# SH1_-_Power.net
KiCad netlist of a schematic drawn in Altium Designer
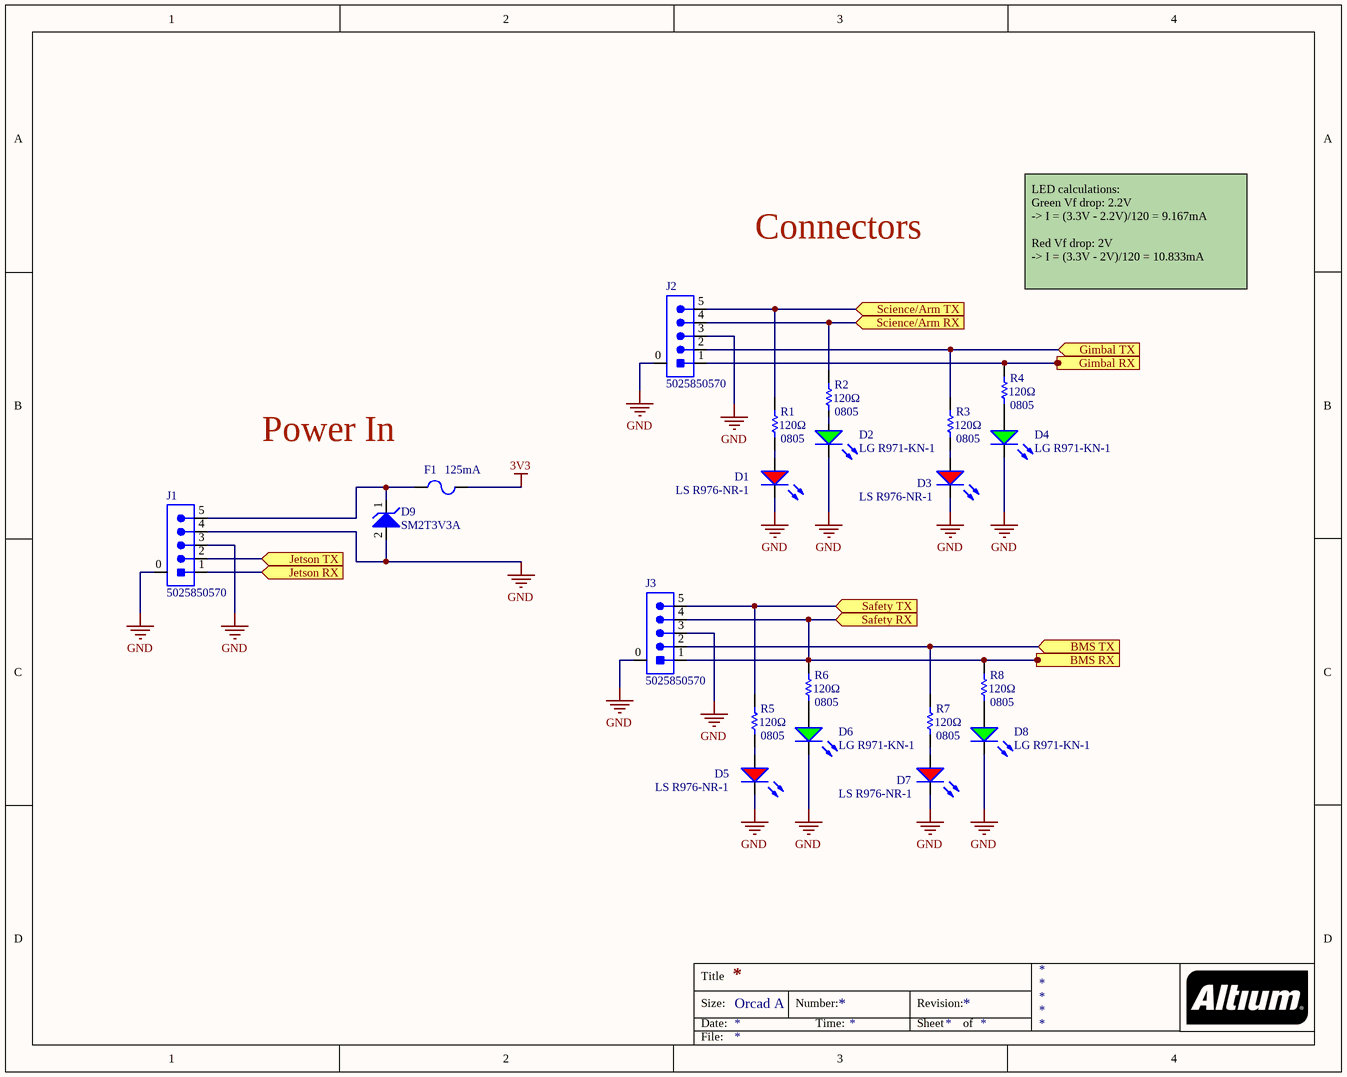
[diagram p0: SH1 - Power.SchDoc]

(export (version "E")
  (design (tool "Eeschema 10.0.6"))
  (components
    (comp (ref "D1")
      (value "LS R976-NR-1")
      (footprint "LED_0805_LINE")
      (description "LED RED DIFFUSED 0805 SMD")
      (fields (field (name "MANUFACTURER PART NUMBER 1") "LS R976-NR-1"))
      (libsource (lib "UWRT_Schematic_Library_2020") (part "DIO_LED_R"))
    )
    (comp (ref "D2")
      (value "LG R971-KN-1")
      (footprint "LED_0805_LINE")
      (description "LED GREEN DIFFUSED 0805 SMD")
      (fields (field (name "MANUFACTURER PART NUMBER 1") "LG R971-KN-1"))
      (libsource (lib "UWRT_Schematic_Library_2020") (part "DIO_LED_G"))
    )
    (comp (ref "D3")
      (value "LS R976-NR-1")
      (footprint "LED_0805_LINE")
      (description "LED RED DIFFUSED 0805 SMD")
      (fields (field (name "MANUFACTURER PART NUMBER 1") "LS R976-NR-1"))
      (libsource (lib "UWRT_Schematic_Library_2020") (part "DIO_LED_R"))
    )
    (comp (ref "D4")
      (value "LG R971-KN-1")
      (footprint "LED_0805_LINE")
      (description "LED GREEN DIFFUSED 0805 SMD")
      (fields (field (name "MANUFACTURER PART NUMBER 1") "LG R971-KN-1"))
      (libsource (lib "UWRT_Schematic_Library_2020") (part "DIO_LED_G"))
    )
    (comp (ref "D5")
      (value "LS R976-NR-1")
      (footprint "LED_0805_LINE")
      (description "LED RED DIFFUSED 0805 SMD")
      (fields (field (name "MANUFACTURER PART NUMBER 1") "LS R976-NR-1"))
      (libsource (lib "UWRT_Schematic_Library_2020") (part "DIO_LED_R"))
    )
    (comp (ref "D6")
      (value "LG R971-KN-1")
      (footprint "LED_0805_LINE")
      (description "LED GREEN DIFFUSED 0805 SMD")
      (fields (field (name "MANUFACTURER PART NUMBER 1") "LG R971-KN-1"))
      (libsource (lib "UWRT_Schematic_Library_2020") (part "DIO_LED_G"))
    )
    (comp (ref "D7")
      (value "LS R976-NR-1")
      (footprint "LED_0805_LINE")
      (description "LED RED DIFFUSED 0805 SMD")
      (fields (field (name "MANUFACTURER PART NUMBER 1") "LS R976-NR-1"))
      (libsource (lib "UWRT_Schematic_Library_2020") (part "DIO_LED_R"))
    )
    (comp (ref "D8")
      (value "LG R971-KN-1")
      (footprint "LED_0805_LINE")
      (description "LED GREEN DIFFUSED 0805 SMD")
      (fields (field (name "MANUFACTURER PART NUMBER 1") "LG R971-KN-1"))
      (libsource (lib "UWRT_Schematic_Library_2020") (part "DIO_LED_G"))
    )
    (comp (ref "D9")
      (value "TVS_DIODE_UNIDIR_3.3V")
      (footprint "TVS_DIODE_UNIDIR")
      (description "TVS DIODE 3.3V 6.8V DO216AA")
      (fields
        (field (name "MANUFACTURER") "STMicroelectronics")
        (field (name "MANUFACTURER PART NUMBER") "SM2T3V3A")
      )
      (libsource (lib "UWRT_Schematic_Library_2020") (part "TVS_DIODE_UNIDIR_3.3V"))
    )
    (comp (ref "F1")
      (value "FUSE_125mA_1206")
      (footprint "FUSE_1206")
      (description "FUSE SMD 125mA 125V")
      (fields (field (name "CURRENT RATING") "125mA"))
      (libsource (lib "UWRT_Schematic_Library_2020") (part "FUSE_125mA_1206"))
    )
    (comp (ref "J1")
      (value "CON_5M_SM_RA")
      (footprint "MOLEX-5025850570")
      (description "CONN HEADER SMD RIGHT ANGLE 1.5MM PITCH")
      (fields (field (name "MANUFACTURER PART NUMBER 1") "5025850570"))
      (libsource (lib "UWRT_Schematic_Library_2020") (part "CON_5M_SM_RA"))
    )
    (comp (ref "J2")
      (value "CON_5M_SM_RA")
      (footprint "MOLEX-5025850570")
      (description "CONN HEADER SMD RIGHT ANGLE 1.5MM PITCH")
      (fields (field (name "MANUFACTURER PART NUMBER 1") "5025850570"))
      (libsource (lib "UWRT_Schematic_Library_2020") (part "CON_5M_SM_RA"))
    )
    (comp (ref "J3")
      (value "CON_5M_SM_RA")
      (footprint "MOLEX-5025850570")
      (description "CONN HEADER SMD RIGHT ANGLE 1.5MM PITCH")
      (fields (field (name "MANUFACTURER PART NUMBER 1") "5025850570"))
      (libsource (lib "UWRT_Schematic_Library_2020") (part "CON_5M_SM_RA"))
    )
    (comp (ref "R1")
      (value "120")
      (footprint "RESC2012X60N")
      (description "RES SMD 120 OHM 1% 1/8W 0805")
      (fields (field (name "CASE CODE (IMPERIAL)") "0805") (field (name "RESISTANCE") "120Ω"))
      (libsource (lib "UWRT_Schematic_Library_2020") (part "RES_120Ω_0805"))
    )
    (comp (ref "R2")
      (value "120")
      (footprint "RESC2012X60N")
      (description "RES SMD 120 OHM 1% 1/8W 0805")
      (fields (field (name "CASE CODE (IMPERIAL)") "0805") (field (name "RESISTANCE") "120Ω"))
      (libsource (lib "UWRT_Schematic_Library_2020") (part "RES_120Ω_0805"))
    )
    (comp (ref "R3")
      (value "120")
      (footprint "RESC2012X60N")
      (description "RES SMD 120 OHM 1% 1/8W 0805")
      (fields (field (name "CASE CODE (IMPERIAL)") "0805") (field (name "RESISTANCE") "120Ω"))
      (libsource (lib "UWRT_Schematic_Library_2020") (part "RES_120Ω_0805"))
    )
    (comp (ref "R4")
      (value "120")
      (footprint "RESC2012X60N")
      (description "RES SMD 120 OHM 1% 1/8W 0805")
      (fields (field (name "CASE CODE (IMPERIAL)") "0805") (field (name "RESISTANCE") "120Ω"))
      (libsource (lib "UWRT_Schematic_Library_2020") (part "RES_120Ω_0805"))
    )
    (comp (ref "R5")
      (value "120")
      (footprint "RESC2012X60N")
      (description "RES SMD 120 OHM 1% 1/8W 0805")
      (fields (field (name "CASE CODE (IMPERIAL)") "0805") (field (name "RESISTANCE") "120Ω"))
      (libsource (lib "UWRT_Schematic_Library_2020") (part "RES_120Ω_0805"))
    )
    (comp (ref "R6")
      (value "120")
      (footprint "RESC2012X60N")
      (description "RES SMD 120 OHM 1% 1/8W 0805")
      (fields (field (name "CASE CODE (IMPERIAL)") "0805") (field (name "RESISTANCE") "120Ω"))
      (libsource (lib "UWRT_Schematic_Library_2020") (part "RES_120Ω_0805"))
    )
    (comp (ref "R7")
      (value "120")
      (footprint "RESC2012X60N")
      (description "RES SMD 120 OHM 1% 1/8W 0805")
      (fields (field (name "CASE CODE (IMPERIAL)") "0805") (field (name "RESISTANCE") "120Ω"))
      (libsource (lib "UWRT_Schematic_Library_2020") (part "RES_120Ω_0805"))
    )
    (comp (ref "R8")
      (value "120")
      (footprint "RESC2012X60N")
      (description "RES SMD 120 OHM 1% 1/8W 0805")
      (fields (field (name "CASE CODE (IMPERIAL)") "0805") (field (name "RESISTANCE") "120Ω"))
      (libsource (lib "UWRT_Schematic_Library_2020") (part "RES_120Ω_0805"))
    )
  )
  (nets
    (net (code "1") (name "/BMS RX") (class "Default")
      (node (ref "J3") (pin "1") (pinfunction "1_1") (pintype "passive"))
      (node (ref "J3") (pin "4") (pinfunction "4_4") (pintype "passive"))
      (node (ref "R6") (pin "1") (pinfunction "1_1") (pintype "passive"))
      (node (ref "R8") (pin "1") (pinfunction "1_1") (pintype "passive"))
    )
    (net (code "2") (name "/BMS TX") (class "Default")
      (node (ref "J3") (pin "2") (pinfunction "2_2") (pintype "passive"))
      (node (ref "R7") (pin "1") (pinfunction "1_1") (pintype "passive"))
    )
    (net (code "3") (name "/Gimbal RX") (class "Default")
      (node (ref "J2") (pin "1") (pinfunction "1_1") (pintype "passive"))
      (node (ref "R4") (pin "1") (pinfunction "1_1") (pintype "passive"))
    )
    (net (code "4") (name "/Gimbal TX") (class "Default")
      (node (ref "J2") (pin "2") (pinfunction "2_2") (pintype "passive"))
      (node (ref "R3") (pin "1") (pinfunction "1_1") (pintype "passive"))
    )
    (net (code "5") (name "/Jetson RX") (class "Default")
      (node (ref "J1") (pin "1") (pinfunction "1_1") (pintype "passive"))
    )
    (net (code "6") (name "/Jetson TX") (class "Default")
      (node (ref "J1") (pin "2") (pinfunction "2_2") (pintype "passive"))
    )
    (net (code "7") (name "/Safety TX") (class "Default")
      (node (ref "J3") (pin "5") (pinfunction "5_5") (pintype "passive"))
      (node (ref "R5") (pin "1") (pinfunction "1_1") (pintype "passive"))
    )
    (net (code "8") (name "/Science{slash}Arm RX") (class "Default")
      (node (ref "J2") (pin "4") (pinfunction "4_4") (pintype "passive"))
      (node (ref "R2") (pin "1") (pinfunction "1_1") (pintype "passive"))
    )
    (net (code "9") (name "/Science{slash}Arm TX") (class "Default")
      (node (ref "J2") (pin "5") (pinfunction "5_5") (pintype "passive"))
      (node (ref "R1") (pin "1") (pinfunction "1_1") (pintype "passive"))
    )
    (net (code "10") (name "3V3") (class "Default")
      (node (ref "F1") (pin "2") (pinfunction "2_2") (pintype "passive"))
    )
    (net (code "11") (name "GND") (class "Default")
      (node (ref "D1") (pin "2") (pinfunction "K_2") (pintype "passive"))
      (node (ref "D2") (pin "2") (pinfunction "K_2") (pintype "passive"))
      (node (ref "D3") (pin "2") (pinfunction "K_2") (pintype "passive"))
      (node (ref "D4") (pin "2") (pinfunction "K_2") (pintype "passive"))
      (node (ref "D5") (pin "2") (pinfunction "K_2") (pintype "passive"))
      (node (ref "D6") (pin "2") (pinfunction "K_2") (pintype "passive"))
      (node (ref "D7") (pin "2") (pinfunction "K_2") (pintype "passive"))
      (node (ref "D8") (pin "2") (pinfunction "K_2") (pintype "passive"))
      (node (ref "D9") (pin "2") (pinfunction "2_2") (pintype "passive"))
      (node (ref "J1") (pin "0") (pinfunction "0_0") (pintype "passive"))
      (node (ref "J1") (pin "3") (pinfunction "3_3") (pintype "passive"))
      (node (ref "J1") (pin "4") (pinfunction "4_4") (pintype "passive"))
      (node (ref "J2") (pin "0") (pinfunction "0_0") (pintype "passive"))
      (node (ref "J2") (pin "3") (pinfunction "3_3") (pintype "passive"))
      (node (ref "J3") (pin "0") (pinfunction "0_0") (pintype "passive"))
      (node (ref "J3") (pin "3") (pinfunction "3_3") (pintype "passive"))
    )
    (net (code "12") (name "Net-(D1-A)") (class "Default")
      (node (ref "D1") (pin "1") (pinfunction "A_1") (pintype "passive"))
      (node (ref "R1") (pin "2") (pinfunction "2_2") (pintype "passive"))
    )
    (net (code "13") (name "Net-(D2-A)") (class "Default")
      (node (ref "D2") (pin "1") (pinfunction "A_1") (pintype "passive"))
      (node (ref "R2") (pin "2") (pinfunction "2_2") (pintype "passive"))
    )
    (net (code "14") (name "Net-(D3-A)") (class "Default")
      (node (ref "D3") (pin "1") (pinfunction "A_1") (pintype "passive"))
      (node (ref "R3") (pin "2") (pinfunction "2_2") (pintype "passive"))
    )
    (net (code "15") (name "Net-(D4-A)") (class "Default")
      (node (ref "D4") (pin "1") (pinfunction "A_1") (pintype "passive"))
      (node (ref "R4") (pin "2") (pinfunction "2_2") (pintype "passive"))
    )
    (net (code "16") (name "Net-(D5-A)") (class "Default")
      (node (ref "D5") (pin "1") (pinfunction "A_1") (pintype "passive"))
      (node (ref "R5") (pin "2") (pinfunction "2_2") (pintype "passive"))
    )
    (net (code "17") (name "Net-(D6-A)") (class "Default")
      (node (ref "D6") (pin "1") (pinfunction "A_1") (pintype "passive"))
      (node (ref "R6") (pin "2") (pinfunction "2_2") (pintype "passive"))
    )
    (net (code "18") (name "Net-(D7-A)") (class "Default")
      (node (ref "D7") (pin "1") (pinfunction "A_1") (pintype "passive"))
      (node (ref "R7") (pin "2") (pinfunction "2_2") (pintype "passive"))
    )
    (net (code "19") (name "Net-(D8-A)") (class "Default")
      (node (ref "D8") (pin "1") (pinfunction "A_1") (pintype "passive"))
      (node (ref "R8") (pin "2") (pinfunction "2_2") (pintype "passive"))
    )
    (net (code "20") (name "Net-(D9-Pad1)") (class "Default")
      (node (ref "D9") (pin "1") (pinfunction "1_1") (pintype "passive"))
      (node (ref "F1") (pin "1") (pinfunction "1_1") (pintype "passive"))
      (node (ref "J1") (pin "5") (pinfunction "5_5") (pintype "passive"))
    )
  )
)
